# ip_phone_d_lcd_keyboard.net
KiCad netlist of a schematic drawn in Altium Designer
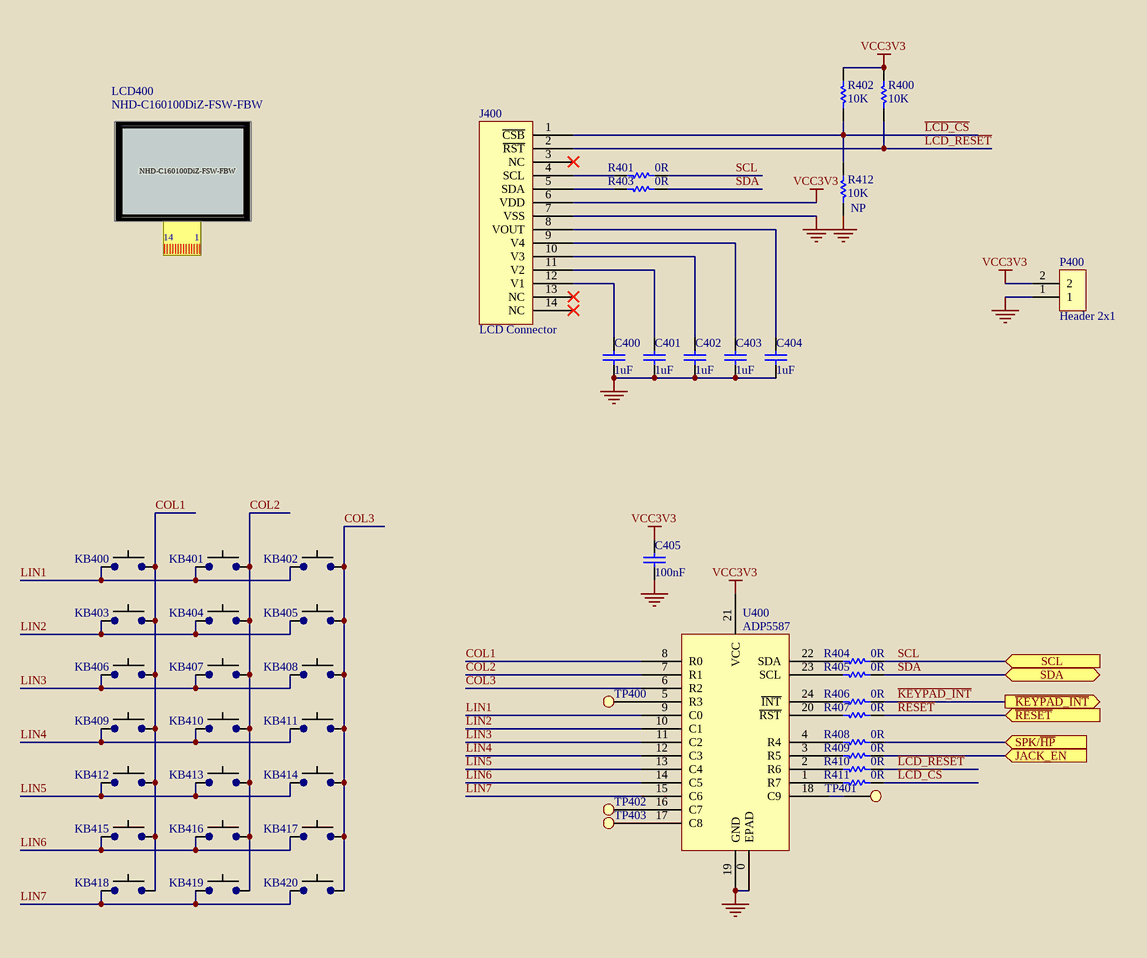
[diagram p0: ip_phone_d_lcd_keyboard.SchDoc]

(export (version "E")
  (design (tool "Eeschema 10.0.6"))
  (components
    (comp (ref "C400")
      (value "1uF")
      (footprint "ip_phone:CC1005-0402")
      (description "CAP CER 1.0UF 6.3V 20% X5R 0402")
      (fields
        (field (name "EVENDORPART#") "490-1319-1-ND")
        (field (name "MANUFACTURER") "Murata Electronics North America")
      )
      (libsource (lib "ip_phone") (part "Capacitor"))
    )
    (comp (ref "C401")
      (value "1uF")
      (footprint "ip_phone:CC1005-0402")
      (description "CAP CER 1.0UF 6.3V 20% X5R 0402")
      (fields
        (field (name "EVENDORPART#") "490-1319-1-ND")
        (field (name "MANUFACTURER") "Murata Electronics North America")
      )
      (libsource (lib "ip_phone") (part "Capacitor"))
    )
    (comp (ref "C402")
      (value "1uF")
      (footprint "ip_phone:CC1005-0402")
      (description "CAP CER 1.0UF 6.3V 20% X5R 0402")
      (fields
        (field (name "EVENDORPART#") "490-1319-1-ND")
        (field (name "MANUFACTURER") "Murata Electronics North America")
      )
      (libsource (lib "ip_phone") (part "Capacitor"))
    )
    (comp (ref "C403")
      (value "1uF")
      (footprint "ip_phone:CC1005-0402")
      (description "CAP CER 1.0UF 6.3V 20% X5R 0402")
      (fields
        (field (name "EVENDORPART#") "490-1319-1-ND")
        (field (name "MANUFACTURER") "Murata Electronics North America")
      )
      (libsource (lib "ip_phone") (part "Capacitor"))
    )
    (comp (ref "C404")
      (value "1uF")
      (footprint "ip_phone:CC1005-0402")
      (description "CAP CER 1.0UF 6.3V 20% X5R 0402")
      (fields
        (field (name "EVENDORPART#") "490-1319-1-ND")
        (field (name "MANUFACTURER") "Murata Electronics North America")
      )
      (libsource (lib "ip_phone") (part "Capacitor"))
    )
    (comp (ref "C405")
      (value "100nF")
      (footprint "ip_phone:CC1005-0402")
      (description "MLCC - SMD/SMT 0.1UF 16V 10% 0402")
      (fields (field (name "EVENDORPART#") "810-C1005X7R1C104K") (field (name "MANUFACTURER") "TDK"))
      (libsource (lib "ip_phone") (part "Capacitor"))
    )
    (comp (ref "J400")
      (value "LCD Connector")
      (footprint "ip_phone:LCD_Connector")
      (fields
        (field (name "EVENDORPART#") "538-52892-1495")
        (field (name "MANUFACTURER") "Molex")
        (field (name "PART#") "52892-1495")
      )
      (libsource (lib "ip_phone") (part "LCD Connector"))
    )
    (comp (ref "KB400")
      (value "Keypad_Button")
      (footprint "ip_phone:Keypad_Button")
      (libsource (lib "ip_phone") (part "Keypad_Button"))
    )
    (comp (ref "KB401")
      (value "Keypad_Button")
      (footprint "ip_phone:Keypad_Button")
      (libsource (lib "ip_phone") (part "Keypad_Button"))
    )
    (comp (ref "KB402")
      (value "Keypad_Button")
      (footprint "ip_phone:Keypad_Button")
      (libsource (lib "ip_phone") (part "Keypad_Button"))
    )
    (comp (ref "KB403")
      (value "Keypad_Button")
      (footprint "ip_phone:Keypad_Button")
      (libsource (lib "ip_phone") (part "Keypad_Button"))
    )
    (comp (ref "KB404")
      (value "Keypad_Button")
      (footprint "ip_phone:Keypad_Button")
      (libsource (lib "ip_phone") (part "Keypad_Button"))
    )
    (comp (ref "KB405")
      (value "Keypad_Button")
      (footprint "ip_phone:Keypad_Button")
      (libsource (lib "ip_phone") (part "Keypad_Button"))
    )
    (comp (ref "KB406")
      (value "Keypad_Button")
      (footprint "ip_phone:Keypad_Button")
      (libsource (lib "ip_phone") (part "Keypad_Button"))
    )
    (comp (ref "KB407")
      (value "Keypad_Button")
      (footprint "ip_phone:Keypad_Button")
      (libsource (lib "ip_phone") (part "Keypad_Button"))
    )
    (comp (ref "KB408")
      (value "Keypad_Button")
      (footprint "ip_phone:Keypad_Button")
      (libsource (lib "ip_phone") (part "Keypad_Button"))
    )
    (comp (ref "KB409")
      (value "Keypad_Button")
      (footprint "ip_phone:Keypad_Button")
      (libsource (lib "ip_phone") (part "Keypad_Button"))
    )
    (comp (ref "KB410")
      (value "Keypad_Button")
      (footprint "ip_phone:Keypad_Button")
      (libsource (lib "ip_phone") (part "Keypad_Button"))
    )
    (comp (ref "KB411")
      (value "Keypad_Button")
      (footprint "ip_phone:Keypad_Button")
      (libsource (lib "ip_phone") (part "Keypad_Button"))
    )
    (comp (ref "KB412")
      (value "Keypad_Button")
      (footprint "ip_phone:Keypad_Button")
      (libsource (lib "ip_phone") (part "Keypad_Button"))
    )
    (comp (ref "KB413")
      (value "Keypad_Button")
      (footprint "ip_phone:Keypad_Button")
      (libsource (lib "ip_phone") (part "Keypad_Button"))
    )
    (comp (ref "KB414")
      (value "Keypad_Button")
      (footprint "ip_phone:Keypad_Button")
      (libsource (lib "ip_phone") (part "Keypad_Button"))
    )
    (comp (ref "KB415")
      (value "Keypad_Button")
      (footprint "ip_phone:Keypad_Button")
      (libsource (lib "ip_phone") (part "Keypad_Button"))
    )
    (comp (ref "KB416")
      (value "Keypad_Button")
      (footprint "ip_phone:Keypad_Button")
      (libsource (lib "ip_phone") (part "Keypad_Button"))
    )
    (comp (ref "KB417")
      (value "Keypad_Button")
      (footprint "ip_phone:Keypad_Button")
      (libsource (lib "ip_phone") (part "Keypad_Button"))
    )
    (comp (ref "KB418")
      (value "Keypad_Button")
      (footprint "ip_phone:Keypad_Button")
      (libsource (lib "ip_phone") (part "Keypad_Button"))
    )
    (comp (ref "KB419")
      (value "Keypad_Button")
      (footprint "ip_phone:Keypad_Button")
      (libsource (lib "ip_phone") (part "Keypad_Button"))
    )
    (comp (ref "KB420")
      (value "Keypad_Button")
      (footprint "ip_phone:Keypad_Button")
      (libsource (lib "ip_phone") (part "Keypad_Button"))
    )
    (comp (ref "LCD400")
      (value "NHD-C160100DiZ-FSW-FBW")
      (description "LCD")
      (fields
        (field (name "EVENDORPART#") "763-C160100DIZFSWFBW")
        (field (name "MANUFACTURER") "Newhaven Display")
      )
      (libsource (lib "ip_phone") (part "LCD"))
    )
    (comp (ref "P400")
      (value "Header 2x1")
      (footprint "ip_phone:HEADER 2X1")
      (description "CONN HEADER SH 2POS SIDE 1MM TIN")
      (fields
        (field (name "EVENDORPART#") "455-1802-1-ND")
        (field (name "MANUFACTURER") "JST Sales America Inc")
      )
      (libsource (lib "ip_phone") (part "CON_HEADER_2X1"))
    )
    (comp (ref "R400")
      (value "10K")
      (footprint "ip_phone:CR1005-0402")
      (description "Thick Film Resistors SMD 0402 10K 5%  1/16 W")
      (fields (field (name "EVENDORPART#") "311-10KJRCT-ND") (field (name "MANUFACTURER") "Yageo"))
      (libsource (lib "ip_phone") (part "Resistor"))
    )
    (comp (ref "R401")
      (value "0R")
      (footprint "ip_phone:CR1005-0402")
      (description "Thick Film Resistors 0402 1/16W Jumper")
      (fields
        (field (name "EVENDORPART#") "667-ERJ-2GE0R00X")
        (field (name "MANUFACTURER") "Panasonic Electronic Components")
      )
      (libsource (lib "ip_phone") (part "Resistor"))
    )
    (comp (ref "R402")
      (value "10K")
      (footprint "ip_phone:CR1005-0402")
      (description "Thick Film Resistors SMD 0402 10K 5%  1/16 W")
      (fields (field (name "EVENDORPART#") "311-10KJRCT-ND") (field (name "MANUFACTURER") "Yageo"))
      (libsource (lib "ip_phone") (part "Resistor"))
    )
    (comp (ref "R403")
      (value "0R")
      (footprint "ip_phone:CR1005-0402")
      (description "Thick Film Resistors 0402 1/16W Jumper")
      (fields
        (field (name "EVENDORPART#") "667-ERJ-2GE0R00X")
        (field (name "MANUFACTURER") "Panasonic Electronic Components")
      )
      (libsource (lib "ip_phone") (part "Resistor"))
    )
    (comp (ref "R404")
      (value "0R")
      (footprint "ip_phone:CR1005-0402")
      (description "Thick Film Resistors 0402 1/16W Jumper")
      (fields
        (field (name "EVENDORPART#") "667-ERJ-2GE0R00X")
        (field (name "MANUFACTURER") "Panasonic Electronic Components")
      )
      (libsource (lib "ip_phone") (part "Resistor"))
    )
    (comp (ref "R405")
      (value "0R")
      (footprint "ip_phone:CR1005-0402")
      (description "Thick Film Resistors 0402 1/16W Jumper")
      (fields
        (field (name "EVENDORPART#") "667-ERJ-2GE0R00X")
        (field (name "MANUFACTURER") "Panasonic Electronic Components")
      )
      (libsource (lib "ip_phone") (part "Resistor"))
    )
    (comp (ref "R406")
      (value "0R")
      (footprint "ip_phone:CR1005-0402")
      (description "Thick Film Resistors 0402 1/16W Jumper")
      (fields
        (field (name "EVENDORPART#") "667-ERJ-2GE0R00X")
        (field (name "MANUFACTURER") "Panasonic Electronic Components")
      )
      (libsource (lib "ip_phone") (part "Resistor"))
    )
    (comp (ref "R407")
      (value "0R")
      (footprint "ip_phone:CR1005-0402")
      (description "Thick Film Resistors 0402 1/16W Jumper")
      (fields
        (field (name "EVENDORPART#") "667-ERJ-2GE0R00X")
        (field (name "MANUFACTURER") "Panasonic Electronic Components")
      )
      (libsource (lib "ip_phone") (part "Resistor"))
    )
    (comp (ref "R408")
      (value "0R")
      (footprint "ip_phone:CR1005-0402")
      (description "Thick Film Resistors 0402 1/16W Jumper")
      (fields
        (field (name "EVENDORPART#") "667-ERJ-2GE0R00X")
        (field (name "MANUFACTURER") "Panasonic Electronic Components")
      )
      (libsource (lib "ip_phone") (part "Resistor"))
    )
    (comp (ref "R409")
      (value "0R")
      (footprint "ip_phone:CR1005-0402")
      (description "Thick Film Resistors 0402 1/16W Jumper")
      (fields
        (field (name "EVENDORPART#") "667-ERJ-2GE0R00X")
        (field (name "MANUFACTURER") "Panasonic Electronic Components")
      )
      (libsource (lib "ip_phone") (part "Resistor"))
    )
    (comp (ref "R410")
      (value "0R")
      (footprint "ip_phone:CR1005-0402")
      (description "Thick Film Resistors 0402 1/16W Jumper")
      (fields
        (field (name "EVENDORPART#") "667-ERJ-2GE0R00X")
        (field (name "MANUFACTURER") "Panasonic Electronic Components")
      )
      (libsource (lib "ip_phone") (part "Resistor"))
    )
    (comp (ref "R411")
      (value "0R")
      (footprint "ip_phone:CR1005-0402")
      (description "Thick Film Resistors 0402 1/16W Jumper")
      (fields
        (field (name "EVENDORPART#") "667-ERJ-2GE0R00X")
        (field (name "MANUFACTURER") "Panasonic Electronic Components")
      )
      (libsource (lib "ip_phone") (part "Resistor"))
    )
    (comp (ref "R412")
      (value "10K")
      (footprint "ip_phone:CR1005-0402")
      (description "Thick Film Resistors SMD 0402 10K 5%  1/16 W")
      (fields
        (field (name "EVENDORPART#") "311-10KJRCT-ND")
        (field (name "MANUFACTURER") "Yageo")
        (field (name "NP") "NP")
      )
      (libsource (lib "ip_phone") (part "Resistor"))
    )
    (comp (ref "TP400")
      (value "Test Point")
      (footprint "ip_phone:Test Point")
      (fields (field (name "EVENDORPART#") "NÃO SE APLICA"))
      (libsource (lib "ip_phone") (part "Test Point"))
    )
    (comp (ref "TP401")
      (value "Test Point")
      (footprint "ip_phone:Test Point")
      (fields (field (name "EVENDORPART#") "NÃO SE APLICA"))
      (libsource (lib "ip_phone") (part "Test Point"))
    )
    (comp (ref "TP402")
      (value "Test Point")
      (footprint "ip_phone:Test Point")
      (fields (field (name "EVENDORPART#") "NÃO SE APLICA"))
      (libsource (lib "ip_phone") (part "Test Point"))
    )
    (comp (ref "TP403")
      (value "Test Point")
      (footprint "ip_phone:Test Point")
      (fields (field (name "EVENDORPART#") "NÃO SE APLICA"))
      (libsource (lib "ip_phone") (part "Test Point"))
    )
    (comp (ref "U400")
      (value "ADP5587")
      (footprint "ip_phone:QFN-24")
      (description "IC Expander/Keyboard Controller")
      (fields (field (name "EVENDORPART#") "ADP5587ACPZ-R7CT-ND") (field (name "PART#") "ADP5587ACPZ-R7"))
      (libsource (lib "ip_phone") (part "ADP5587"))
    )
  )
  (nets
    (net (code "1") (name "/COL1") (class "Default")
      (node (ref "KB400") (pin "2") (pinfunction "2_2") (pintype "passive"))
      (node (ref "KB403") (pin "2") (pinfunction "2_2") (pintype "passive"))
      (node (ref "KB406") (pin "2") (pinfunction "2_2") (pintype "passive"))
      (node (ref "KB409") (pin "2") (pinfunction "2_2") (pintype "passive"))
      (node (ref "KB412") (pin "2") (pinfunction "2_2") (pintype "passive"))
      (node (ref "KB415") (pin "2") (pinfunction "2_2") (pintype "passive"))
      (node (ref "KB418") (pin "2") (pinfunction "2_2") (pintype "passive"))
      (node (ref "U400") (pin "8") (pinfunction "R0_8") (pintype "passive"))
    )
    (net (code "2") (name "/COL2") (class "Default")
      (node (ref "KB401") (pin "2") (pinfunction "2_2") (pintype "passive"))
      (node (ref "KB404") (pin "2") (pinfunction "2_2") (pintype "passive"))
      (node (ref "KB407") (pin "2") (pinfunction "2_2") (pintype "passive"))
      (node (ref "KB410") (pin "2") (pinfunction "2_2") (pintype "passive"))
      (node (ref "KB413") (pin "2") (pinfunction "2_2") (pintype "passive"))
      (node (ref "KB416") (pin "2") (pinfunction "2_2") (pintype "passive"))
      (node (ref "KB419") (pin "2") (pinfunction "2_2") (pintype "passive"))
      (node (ref "U400") (pin "7") (pinfunction "R1_7") (pintype "passive"))
    )
    (net (code "3") (name "/COL3") (class "Default")
      (node (ref "KB402") (pin "2") (pinfunction "2_2") (pintype "passive"))
      (node (ref "KB405") (pin "2") (pinfunction "2_2") (pintype "passive"))
      (node (ref "KB408") (pin "2") (pinfunction "2_2") (pintype "passive"))
      (node (ref "KB411") (pin "2") (pinfunction "2_2") (pintype "passive"))
      (node (ref "KB414") (pin "2") (pinfunction "2_2") (pintype "passive"))
      (node (ref "KB417") (pin "2") (pinfunction "2_2") (pintype "passive"))
      (node (ref "KB420") (pin "2") (pinfunction "2_2") (pintype "passive"))
      (node (ref "U400") (pin "6") (pinfunction "R2_6") (pintype "passive"))
    )
    (net (code "4") (name "/JACK_EN") (class "Default")
      (node (ref "R409") (pin "1") (pinfunction "1_1") (pintype "passive"))
    )
    (net (code "5") (name "/LIN1") (class "Default")
      (node (ref "KB400") (pin "1") (pinfunction "1_1") (pintype "passive"))
      (node (ref "KB401") (pin "1") (pinfunction "1_1") (pintype "passive"))
      (node (ref "KB402") (pin "1") (pinfunction "1_1") (pintype "passive"))
      (node (ref "U400") (pin "9") (pinfunction "C0_9") (pintype "passive"))
    )
    (net (code "6") (name "/LIN2") (class "Default")
      (node (ref "KB403") (pin "1") (pinfunction "1_1") (pintype "passive"))
      (node (ref "KB404") (pin "1") (pinfunction "1_1") (pintype "passive"))
      (node (ref "KB405") (pin "1") (pinfunction "1_1") (pintype "passive"))
      (node (ref "U400") (pin "10") (pinfunction "C1_10") (pintype "passive"))
    )
    (net (code "7") (name "/LIN3") (class "Default")
      (node (ref "KB406") (pin "1") (pinfunction "1_1") (pintype "passive"))
      (node (ref "KB407") (pin "1") (pinfunction "1_1") (pintype "passive"))
      (node (ref "KB408") (pin "1") (pinfunction "1_1") (pintype "passive"))
      (node (ref "U400") (pin "11") (pinfunction "C2_11") (pintype "passive"))
    )
    (net (code "8") (name "/LIN4") (class "Default")
      (node (ref "KB409") (pin "1") (pinfunction "1_1") (pintype "passive"))
      (node (ref "KB410") (pin "1") (pinfunction "1_1") (pintype "passive"))
      (node (ref "KB411") (pin "1") (pinfunction "1_1") (pintype "passive"))
      (node (ref "U400") (pin "12") (pinfunction "C3_12") (pintype "passive"))
    )
    (net (code "9") (name "/LIN5") (class "Default")
      (node (ref "KB412") (pin "1") (pinfunction "1_1") (pintype "passive"))
      (node (ref "KB413") (pin "1") (pinfunction "1_1") (pintype "passive"))
      (node (ref "KB414") (pin "1") (pinfunction "1_1") (pintype "passive"))
      (node (ref "U400") (pin "13") (pinfunction "C4_13") (pintype "passive"))
    )
    (net (code "10") (name "/LIN6") (class "Default")
      (node (ref "KB415") (pin "1") (pinfunction "1_1") (pintype "passive"))
      (node (ref "KB416") (pin "1") (pinfunction "1_1") (pintype "passive"))
      (node (ref "KB417") (pin "1") (pinfunction "1_1") (pintype "passive"))
      (node (ref "U400") (pin "14") (pinfunction "C5_14") (pintype "passive"))
    )
    (net (code "11") (name "/LIN7") (class "Default")
      (node (ref "KB418") (pin "1") (pinfunction "1_1") (pintype "passive"))
      (node (ref "KB419") (pin "1") (pinfunction "1_1") (pintype "passive"))
      (node (ref "KB420") (pin "1") (pinfunction "1_1") (pintype "passive"))
      (node (ref "U400") (pin "15") (pinfunction "C6_15") (pintype "passive"))
    )
    (net (code "12") (name "/SCL") (class "Default")
      (node (ref "R401") (pin "1") (pinfunction "1_1") (pintype "passive"))
      (node (ref "R404") (pin "1") (pinfunction "1_1") (pintype "passive"))
    )
    (net (code "13") (name "/SDA") (class "Default")
      (node (ref "R403") (pin "1") (pinfunction "1_1") (pintype "passive"))
      (node (ref "R405") (pin "1") (pinfunction "1_1") (pintype "passive"))
    )
    (net (code "14") (name "/SPK{slash}~{HP}") (class "Default")
      (node (ref "R408") (pin "1") (pinfunction "1_1") (pintype "passive"))
    )
    (net (code "15") (name "/~{KEYPAD_INT}") (class "Default")
      (node (ref "R406") (pin "1") (pinfunction "1_1") (pintype "passive"))
    )
    (net (code "16") (name "/~{LCD_CS}") (class "Default")
      (node (ref "J400") (pin "1") (pinfunction "~{CSB}_1") (pintype "passive"))
      (node (ref "R402") (pin "1") (pinfunction "1_1") (pintype "passive"))
      (node (ref "R411") (pin "1") (pinfunction "1_1") (pintype "passive"))
      (node (ref "R412") (pin "2") (pinfunction "2_2") (pintype "passive"))
    )
    (net (code "17") (name "/~{LCD_RESET}") (class "Default")
      (node (ref "J400") (pin "2") (pinfunction "~{RST}_2") (pintype "passive"))
      (node (ref "R400") (pin "1") (pinfunction "1_1") (pintype "passive"))
      (node (ref "R410") (pin "1") (pinfunction "1_1") (pintype "passive"))
    )
    (net (code "18") (name "/~{RESET}") (class "Default")
      (node (ref "R407") (pin "1") (pinfunction "1_1") (pintype "passive"))
    )
    (net (code "19") (name "GND") (class "Default")
      (node (ref "C400") (pin "2") (pinfunction "2_2") (pintype "passive"))
      (node (ref "C401") (pin "2") (pinfunction "2_2") (pintype "passive"))
      (node (ref "C402") (pin "2") (pinfunction "2_2") (pintype "passive"))
      (node (ref "C403") (pin "2") (pinfunction "2_2") (pintype "passive"))
      (node (ref "C404") (pin "2") (pinfunction "2_2") (pintype "passive"))
      (node (ref "C405") (pin "1") (pinfunction "1_1") (pintype "passive"))
      (node (ref "J400") (pin "7") (pinfunction "VSS_7") (pintype "passive"))
      (node (ref "P400") (pin "1") (pinfunction "1_1") (pintype "passive"))
      (node (ref "R412") (pin "1") (pinfunction "1_1") (pintype "passive"))
      (node (ref "U400") (pin "0") (pinfunction "EPAD_0") (pintype "passive"))
      (node (ref "U400") (pin "19") (pinfunction "GND_19") (pintype "passive"))
    )
    (net (code "20") (name "Net-(J400-SCL)") (class "Default")
      (node (ref "J400") (pin "4") (pinfunction "SCL_4") (pintype "passive"))
      (node (ref "R401") (pin "2") (pinfunction "2_2") (pintype "passive"))
    )
    (net (code "21") (name "Net-(J400-SDA)") (class "Default")
      (node (ref "J400") (pin "5") (pinfunction "SDA_5") (pintype "passive"))
      (node (ref "R403") (pin "2") (pinfunction "2_2") (pintype "passive"))
    )
    (net (code "22") (name "Net-(J400-V1)") (class "Default")
      (node (ref "C400") (pin "1") (pinfunction "1_1") (pintype "passive"))
      (node (ref "J400") (pin "12") (pinfunction "V1_12") (pintype "passive"))
    )
    (net (code "23") (name "Net-(J400-V2)") (class "Default")
      (node (ref "C401") (pin "1") (pinfunction "1_1") (pintype "passive"))
      (node (ref "J400") (pin "11") (pinfunction "V2_11") (pintype "passive"))
    )
    (net (code "24") (name "Net-(J400-V3)") (class "Default")
      (node (ref "C402") (pin "1") (pinfunction "1_1") (pintype "passive"))
      (node (ref "J400") (pin "10") (pinfunction "V3_10") (pintype "passive"))
    )
    (net (code "25") (name "Net-(J400-V4)") (class "Default")
      (node (ref "C403") (pin "1") (pinfunction "1_1") (pintype "passive"))
      (node (ref "J400") (pin "9") (pinfunction "V4_9") (pintype "passive"))
    )
    (net (code "26") (name "Net-(J400-VOUT)") (class "Default")
      (node (ref "C404") (pin "1") (pinfunction "1_1") (pintype "passive"))
      (node (ref "J400") (pin "8") (pinfunction "VOUT_8") (pintype "passive"))
    )
    (net (code "27") (name "Net-(U400-C7)") (class "Default")
      (node (ref "TP402") (pin "1") (pinfunction "1_1") (pintype "passive"))
      (node (ref "U400") (pin "16") (pinfunction "C7_16") (pintype "passive"))
    )
    (net (code "28") (name "Net-(U400-C8)") (class "Default")
      (node (ref "TP403") (pin "1") (pinfunction "1_1") (pintype "passive"))
      (node (ref "U400") (pin "17") (pinfunction "C8_17") (pintype "passive"))
    )
    (net (code "29") (name "Net-(U400-C9)") (class "Default")
      (node (ref "TP401") (pin "1") (pinfunction "1_1") (pintype "passive"))
      (node (ref "U400") (pin "18") (pinfunction "C9_18") (pintype "passive"))
    )
    (net (code "30") (name "Net-(U400-R3)") (class "Default")
      (node (ref "TP400") (pin "1") (pinfunction "1_1") (pintype "passive"))
      (node (ref "U400") (pin "5") (pinfunction "R3_5") (pintype "passive"))
    )
    (net (code "31") (name "Net-(U400-R4)") (class "Default")
      (node (ref "R408") (pin "2") (pinfunction "2_2") (pintype "passive"))
      (node (ref "U400") (pin "4") (pinfunction "R4_4") (pintype "passive"))
    )
    (net (code "32") (name "Net-(U400-R5)") (class "Default")
      (node (ref "R409") (pin "2") (pinfunction "2_2") (pintype "passive"))
      (node (ref "U400") (pin "3") (pinfunction "R5_3") (pintype "passive"))
    )
    (net (code "33") (name "Net-(U400-R6)") (class "Default")
      (node (ref "R410") (pin "2") (pinfunction "2_2") (pintype "passive"))
      (node (ref "U400") (pin "2") (pinfunction "R6_2") (pintype "passive"))
    )
    (net (code "34") (name "Net-(U400-R7)") (class "Default")
      (node (ref "R411") (pin "2") (pinfunction "2_2") (pintype "passive"))
      (node (ref "U400") (pin "1") (pinfunction "R7_1") (pintype "passive"))
    )
    (net (code "35") (name "Net-(U400-SCL)") (class "Default")
      (node (ref "R405") (pin "2") (pinfunction "2_2") (pintype "passive"))
      (node (ref "U400") (pin "23") (pinfunction "SCL_23") (pintype "passive"))
    )
    (net (code "36") (name "Net-(U400-SDA)") (class "Default")
      (node (ref "R404") (pin "2") (pinfunction "2_2") (pintype "passive"))
      (node (ref "U400") (pin "22") (pinfunction "SDA_22") (pintype "passive"))
    )
    (net (code "37") (name "Net-(U400-~{INT})") (class "Default")
      (node (ref "R406") (pin "2") (pinfunction "2_2") (pintype "passive"))
      (node (ref "U400") (pin "24") (pinfunction "~{INT}_24") (pintype "passive"))
    )
    (net (code "38") (name "Net-(U400-~{RST})") (class "Default")
      (node (ref "R407") (pin "2") (pinfunction "2_2") (pintype "passive"))
      (node (ref "U400") (pin "20") (pinfunction "~{RST}_20") (pintype "passive"))
    )
    (net (code "39") (name "VCC3V3") (class "Default")
      (node (ref "C405") (pin "2") (pinfunction "2_2") (pintype "passive"))
      (node (ref "J400") (pin "6") (pinfunction "VDD_6") (pintype "passive"))
      (node (ref "P400") (pin "2") (pinfunction "2_2") (pintype "passive"))
      (node (ref "R400") (pin "2") (pinfunction "2_2") (pintype "passive"))
      (node (ref "R402") (pin "2") (pinfunction "2_2") (pintype "passive"))
      (node (ref "U400") (pin "21") (pinfunction "VCC_21") (pintype "passive"))
    )
    (net (code "40") (name "unconnected-(J400-NC-Pad3)") (class "Default")
      (node (ref "J400") (pin "3") (pinfunction "NC_3") (pintype "passive+no_connect"))
    )
    (net (code "41") (name "unconnected-(J400-NC-Pad13)") (class "Default")
      (node (ref "J400") (pin "13") (pinfunction "NC_13") (pintype "passive+no_connect"))
    )
    (net (code "42") (name "unconnected-(J400-NC-Pad14)") (class "Default")
      (node (ref "J400") (pin "14") (pinfunction "NC_14") (pintype "passive+no_connect"))
    )
  )
)
